# webradio.net
KiCad netlist of a schematic drawn in EAGLE
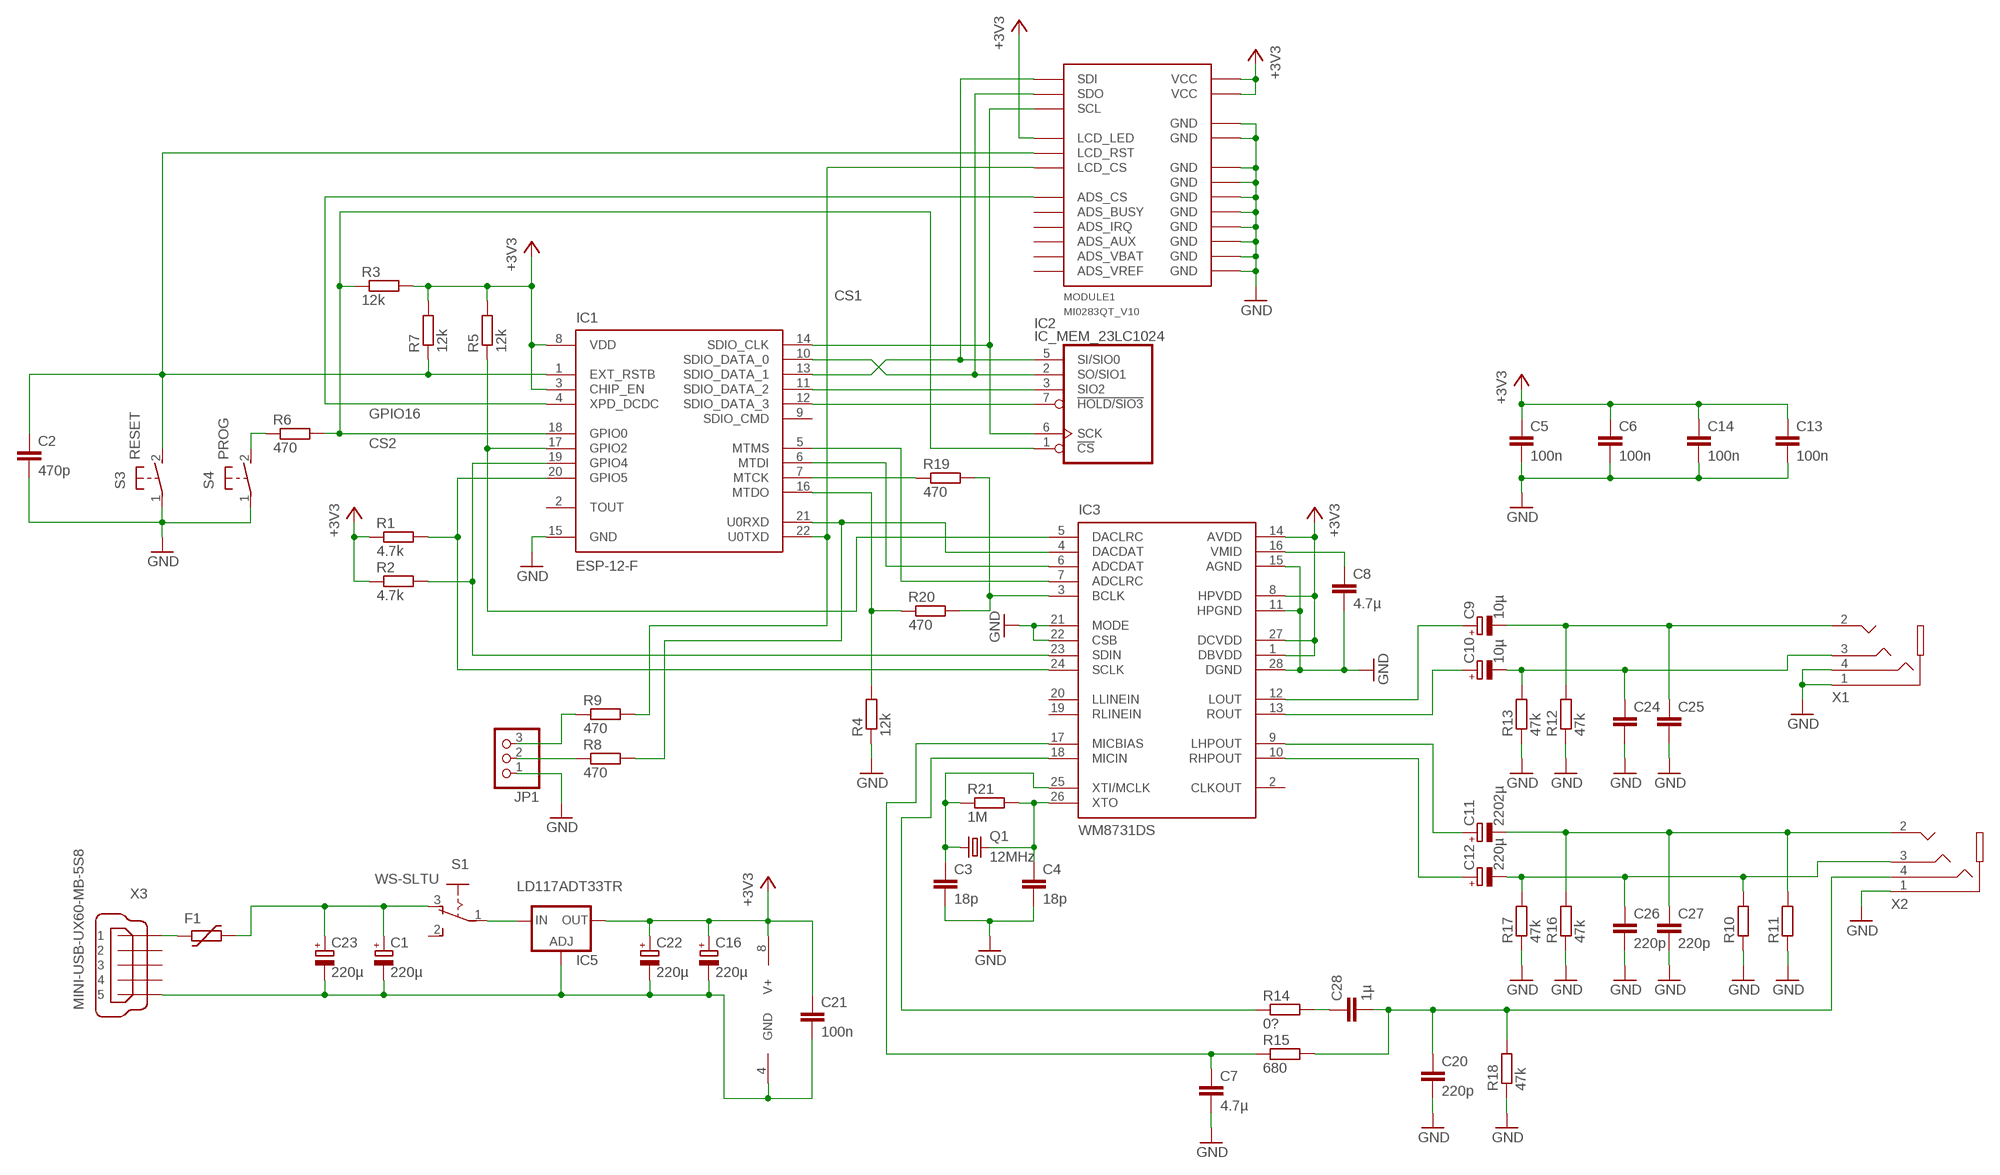
[diagram p0: schematic, sheet 1]

(export (version "E")
  (design (tool "Eeschema 10.0.6"))
  (components
    (comp (ref "C1")
      (value "220µ")
      (footprint "eagle-import:B_3528-21R")
      (libsource (lib "eagle-import") (part "CPOL-EUB/3528-21R"))
    )
    (comp (ref "C2")
      (value "470p")
      (footprint "eagle-import:C0805")
      (libsource (lib "eagle-import") (part "C-EUC0805"))
    )
    (comp (ref "C3")
      (value "18p")
      (footprint "eagle-import:C0805")
      (libsource (lib "eagle-import") (part "C-EUC0805"))
    )
    (comp (ref "C4")
      (value "18p")
      (footprint "eagle-import:C0805")
      (libsource (lib "eagle-import") (part "C-EUC0805"))
    )
    (comp (ref "C5")
      (value "100n")
      (footprint "eagle-import:C0805")
      (libsource (lib "eagle-import") (part "C-EUC0805"))
    )
    (comp (ref "C6")
      (value "100n")
      (footprint "eagle-import:C0805")
      (libsource (lib "eagle-import") (part "C-EUC0805"))
    )
    (comp (ref "C7")
      (value "4.7µ")
      (footprint "eagle-import:C0805")
      (libsource (lib "eagle-import") (part "C-EUC0805"))
    )
    (comp (ref "C8")
      (value "4.7µ")
      (footprint "eagle-import:C0805")
      (libsource (lib "eagle-import") (part "C-EUC0805"))
    )
    (comp (ref "C9")
      (value "10µ")
      (footprint "eagle-import:A_3216-18R")
      (libsource (lib "eagle-import") (part "CPOL-EUA/3216-18R"))
    )
    (comp (ref "C10")
      (value "10µ")
      (footprint "eagle-import:A_3216-18R")
      (libsource (lib "eagle-import") (part "CPOL-EUA/3216-18R"))
    )
    (comp (ref "C11")
      (value "2202µ")
      (footprint "eagle-import:D_7343-31R")
      (libsource (lib "eagle-import") (part "CPOL-EUD/7343-31R"))
    )
    (comp (ref "C12")
      (value "220µ")
      (footprint "eagle-import:D_7343-31R")
      (libsource (lib "eagle-import") (part "CPOL-EUD/7343-31R"))
    )
    (comp (ref "C13")
      (value "100n")
      (footprint "eagle-import:C0805")
      (libsource (lib "eagle-import") (part "C-EUC0805"))
    )
    (comp (ref "C14")
      (value "100n")
      (footprint "eagle-import:C0805")
      (libsource (lib "eagle-import") (part "C-EUC0805"))
    )
    (comp (ref "C16")
      (value "220µ")
      (footprint "eagle-import:B_3528-21R")
      (libsource (lib "eagle-import") (part "CPOL-EUB/3528-21R"))
    )
    (comp (ref "C20")
      (value "220p")
      (footprint "eagle-import:C0805")
      (libsource (lib "eagle-import") (part "C-EUC0805"))
    )
    (comp (ref "C21")
      (value "100n")
      (footprint "eagle-import:C0805")
      (libsource (lib "eagle-import") (part "C-EUC0805"))
    )
    (comp (ref "C22")
      (value "220µ")
      (footprint "eagle-import:B_3528-21R")
      (libsource (lib "eagle-import") (part "CPOL-EUB/3528-21R"))
    )
    (comp (ref "C23")
      (value "220µ")
      (footprint "eagle-import:B_3528-21R")
      (libsource (lib "eagle-import") (part "CPOL-EUB/3528-21R"))
    )
    (comp (ref "C24")
      (value "C-EUC0805")
      (footprint "eagle-import:C0805")
      (libsource (lib "eagle-import") (part "C-EUC0805"))
    )
    (comp (ref "C25")
      (value "C-EUC0805")
      (footprint "eagle-import:C0805")
      (libsource (lib "eagle-import") (part "C-EUC0805"))
    )
    (comp (ref "C26")
      (value "220p")
      (footprint "eagle-import:C0805")
      (libsource (lib "eagle-import") (part "C-EUC0805"))
    )
    (comp (ref "C27")
      (value "220p")
      (footprint "eagle-import:C0805")
      (libsource (lib "eagle-import") (part "C-EUC0805"))
    )
    (comp (ref "C28")
      (value "1µ")
      (footprint "eagle-import:C0805")
      (libsource (lib "eagle-import") (part "C-EUC0805"))
    )
    (comp (ref "F1")
      (value "FUSE_PTC-1812")
      (footprint "eagle-import:PTC1812L")
      (libsource (lib "eagle-import") (part "FUSE_PTC-1812"))
    )
    (comp (ref "IC1")
      (value "ESP-12-F")
      (footprint "eagle-import:ESP-12-F")
      (libsource (lib "eagle-import") (part "ESP-12-F"))
    )
    (comp (ref "IC2")
      (value "IC_MEM_23LC1024")
      (footprint "eagle-import:SOIC-8")
      (libsource (lib "eagle-import") (part "IC_MEM_23LC1024"))
    )
    (comp (ref "IC3")
      (value "WM8731DS")
      (footprint "eagle-import:SSOP28")
      (libsource (lib "eagle-import") (part "WM8731DS"))
    )
    (comp (ref "IC5")
      (value "LD117ADT33TR")
      (footprint "eagle-import:DPACK")
      (libsource (lib "eagle-import") (part "LD117A?DT33TR"))
    )
    (comp (ref "JP1")
      (value "PINHD-1X3/90")
      (footprint "eagle-import:1X03_90")
      (libsource (lib "eagle-import") (part "PINHD-1X3/90"))
    )
    (comp (ref "MODULE1")
      (value "MI0283QT_V10")
      (footprint "eagle-import:MI0283QT_V10")
      (libsource (lib "eagle-import") (part "MI0283QT_V10"))
    )
    (comp (ref "Q1")
      (value "12MHz")
      (footprint "eagle-import:HC49UP")
      (libsource (lib "eagle-import") (part "CRYSTALHC49UP"))
    )
    (comp (ref "R1")
      (value "4.7k")
      (footprint "eagle-import:R0805")
      (libsource (lib "eagle-import") (part "R-EU_R0805"))
    )
    (comp (ref "R2")
      (value "4.7k")
      (footprint "eagle-import:R0805")
      (libsource (lib "eagle-import") (part "R-EU_R0805"))
    )
    (comp (ref "R3")
      (value "12k")
      (footprint "eagle-import:R0805")
      (libsource (lib "eagle-import") (part "R-EU_R0805"))
    )
    (comp (ref "R4")
      (value "12k")
      (footprint "eagle-import:R0805")
      (libsource (lib "eagle-import") (part "R-EU_R0805"))
    )
    (comp (ref "R5")
      (value "12k")
      (footprint "eagle-import:R0805")
      (libsource (lib "eagle-import") (part "R-EU_R0805"))
    )
    (comp (ref "R6")
      (value "470")
      (footprint "eagle-import:R0805")
      (libsource (lib "eagle-import") (part "R-EU_R0805"))
    )
    (comp (ref "R7")
      (value "12k")
      (footprint "eagle-import:R0805")
      (libsource (lib "eagle-import") (part "R-EU_R0805"))
    )
    (comp (ref "R8")
      (value "470")
      (footprint "eagle-import:R0805")
      (libsource (lib "eagle-import") (part "R-EU_R0805"))
    )
    (comp (ref "R9")
      (value "470")
      (footprint "eagle-import:R0805")
      (libsource (lib "eagle-import") (part "R-EU_R0805"))
    )
    (comp (ref "R10")
      (value "R-EU_R0805")
      (footprint "eagle-import:R0805")
      (libsource (lib "eagle-import") (part "R-EU_R0805"))
    )
    (comp (ref "R11")
      (value "R-EU_R0805")
      (footprint "eagle-import:R0805")
      (libsource (lib "eagle-import") (part "R-EU_R0805"))
    )
    (comp (ref "R12")
      (value "47k")
      (footprint "eagle-import:R0805")
      (libsource (lib "eagle-import") (part "R-EU_R0805"))
    )
    (comp (ref "R13")
      (value "47k")
      (footprint "eagle-import:R0805")
      (libsource (lib "eagle-import") (part "R-EU_R0805"))
    )
    (comp (ref "R14")
      (value "0?")
      (footprint "eagle-import:R0805")
      (libsource (lib "eagle-import") (part "R-EU_R0805"))
    )
    (comp (ref "R15")
      (value "680")
      (footprint "eagle-import:R0805")
      (libsource (lib "eagle-import") (part "R-EU_R0805"))
    )
    (comp (ref "R16")
      (value "47k")
      (footprint "eagle-import:R0805")
      (libsource (lib "eagle-import") (part "R-EU_R0805"))
    )
    (comp (ref "R17")
      (value "47k")
      (footprint "eagle-import:R0805")
      (libsource (lib "eagle-import") (part "R-EU_R0805"))
    )
    (comp (ref "R18")
      (value "47k")
      (footprint "eagle-import:R0805")
      (libsource (lib "eagle-import") (part "R-EU_R0805"))
    )
    (comp (ref "R19")
      (value "470")
      (footprint "eagle-import:R0805")
      (libsource (lib "eagle-import") (part "R-EU_R0805"))
    )
    (comp (ref "R20")
      (value "470")
      (footprint "eagle-import:R0805")
      (libsource (lib "eagle-import") (part "R-EU_R0805"))
    )
    (comp (ref "R21")
      (value "1M")
      (footprint "eagle-import:R0805")
      (libsource (lib "eagle-import") (part "R-EU_R0805"))
    )
    (comp (ref "S1")
      (value "WS-SLTU")
      (footprint "eagle-import:450302014072")
      (libsource (lib "eagle-import") (part "WS-SLTU"))
    )
    (comp (ref "S3")
      (value "RESET")
      (footprint "eagle-import:B3F-31XX")
      (libsource (lib "eagle-import") (part "31-XX"))
    )
    (comp (ref "S4")
      (value "PROG")
      (footprint "eagle-import:B3F-31XX")
      (libsource (lib "eagle-import") (part "31-XX"))
    )
    (comp (ref "X1")
      (value "SJ-43514-SMT")
      (footprint "eagle-import:SJ-43514-SMT")
      (libsource (lib "eagle-import") (part "SJ-43514-SMT"))
    )
    (comp (ref "X2")
      (value "SJ-43514-SMT")
      (footprint "eagle-import:SJ-43514-SMT")
      (libsource (lib "eagle-import") (part "SJ-43514-SMT"))
    )
    (comp (ref "X3")
      (value "MINI-USB-UX60-MB-5S8")
      (footprint "eagle-import:UX60-MB-5S8")
      (libsource (lib "eagle-import") (part "MINI-USB-UX60-MB-5S8"))
    )
  )
  (nets
    (net (code "1") (name "+3V3") (class "Default")
      (node (ref "C13") (pin "1") (pinfunction "1_1") (pintype "passive"))
      (node (ref "C14") (pin "1") (pinfunction "1_1") (pintype "passive"))
      (node (ref "C16") (pin "+") (pinfunction "+_+") (pintype "passive"))
      (node (ref "C21") (pin "1") (pinfunction "1_1") (pintype "passive"))
      (node (ref "C22") (pin "+") (pinfunction "+_+") (pintype "passive"))
      (node (ref "C5") (pin "1") (pinfunction "1_1") (pintype "passive"))
      (node (ref "C6") (pin "1") (pinfunction "1_1") (pintype "passive"))
      (node (ref "IC1") (pin "3") (pinfunction "CHIP_EN_3") (pintype "input"))
      (node (ref "IC1") (pin "8") (pinfunction "VDD_8") (pintype "power_in"))
      (node (ref "IC2") (pin "8") (pinfunction "V+_8") (pintype "power_in"))
      (node (ref "IC3") (pin "1") (pinfunction "DBVDD_1") (pintype "power_in"))
      (node (ref "IC3") (pin "14") (pinfunction "AVDD_14") (pintype "power_in"))
      (node (ref "IC3") (pin "27") (pinfunction "DCVDD_27") (pintype "power_in"))
      (node (ref "IC3") (pin "8") (pinfunction "HPVDD_8") (pintype "power_in"))
      (node (ref "IC5") (pin "4") (pinfunction "OUT_4") (pintype "passive"))
      (node (ref "MODULE1") (pin "3_VCC") (pinfunction "VCC_3_VCC") (pintype "power_in"))
      (node (ref "MODULE1") (pin "4_VCC") (pinfunction "VCC_4_VCC") (pintype "power_in"))
      (node (ref "MODULE1") (pin "5_LCD_LED") (pinfunction "LCD_LED_5_LCD_LED") (pintype "input"))
      (node (ref "R1") (pin "1") (pinfunction "1_1") (pintype "passive"))
      (node (ref "R2") (pin "1") (pinfunction "1_1") (pintype "passive"))
      (node (ref "R3") (pin "2") (pinfunction "2_2") (pintype "passive"))
      (node (ref "R5") (pin "2") (pinfunction "2_2") (pintype "passive"))
      (node (ref "R7") (pin "2") (pinfunction "2_2") (pintype "passive"))
    )
    (net (code "2") (name "GND") (class "Default")
      (node (ref "C1") (pin "-") (pinfunction "-_-") (pintype "passive"))
      (node (ref "C13") (pin "2") (pinfunction "2_2") (pintype "passive"))
      (node (ref "C14") (pin "2") (pinfunction "2_2") (pintype "passive"))
      (node (ref "C16") (pin "-") (pinfunction "-_-") (pintype "passive"))
      (node (ref "C2") (pin "2") (pinfunction "2_2") (pintype "passive"))
      (node (ref "C20") (pin "2") (pinfunction "2_2") (pintype "passive"))
      (node (ref "C21") (pin "2") (pinfunction "2_2") (pintype "passive"))
      (node (ref "C22") (pin "-") (pinfunction "-_-") (pintype "passive"))
      (node (ref "C23") (pin "-") (pinfunction "-_-") (pintype "passive"))
      (node (ref "C24") (pin "2") (pinfunction "2_2") (pintype "passive"))
      (node (ref "C25") (pin "2") (pinfunction "2_2") (pintype "passive"))
      (node (ref "C26") (pin "2") (pinfunction "2_2") (pintype "passive"))
      (node (ref "C27") (pin "2") (pinfunction "2_2") (pintype "passive"))
      (node (ref "C3") (pin "2") (pinfunction "2_2") (pintype "passive"))
      (node (ref "C4") (pin "2") (pinfunction "2_2") (pintype "passive"))
      (node (ref "C5") (pin "2") (pinfunction "2_2") (pintype "passive"))
      (node (ref "C6") (pin "2") (pinfunction "2_2") (pintype "passive"))
      (node (ref "C7") (pin "2") (pinfunction "2_2") (pintype "passive"))
      (node (ref "C8") (pin "2") (pinfunction "2_2") (pintype "passive"))
      (node (ref "IC1") (pin "15") (pinfunction "GND_15") (pintype "power_in"))
      (node (ref "IC2") (pin "4") (pinfunction "GND_4") (pintype "power_in"))
      (node (ref "IC3") (pin "11") (pinfunction "HPGND_11") (pintype "power_in"))
      (node (ref "IC3") (pin "15") (pinfunction "AGND_15") (pintype "power_in"))
      (node (ref "IC3") (pin "21") (pinfunction "MODE_21") (pintype "input"))
      (node (ref "IC3") (pin "22") (pinfunction "CSB_22") (pintype "input"))
      (node (ref "IC3") (pin "28") (pinfunction "DGND_28") (pintype "power_in"))
      (node (ref "IC5") (pin "1") (pinfunction "ADJ_1") (pintype "input"))
      (node (ref "JP1") (pin "1") (pinfunction "1_1") (pintype "passive"))
      (node (ref "MODULE1") (pin "1_GND") (pinfunction "GND_1_GND") (pintype "power_in"))
      (node (ref "MODULE1") (pin "2_GND") (pinfunction "GND_2_GND") (pintype "power_in"))
      (node (ref "MODULE1") (pin "GND_1") (pinfunction "GND_GND_1") (pintype "power_in"))
      (node (ref "MODULE1") (pin "GND_2") (pinfunction "GND_GND_2") (pintype "power_in"))
      (node (ref "MODULE1") (pin "GND_3") (pinfunction "GND_GND_3") (pintype "power_in"))
      (node (ref "MODULE1") (pin "GND_4") (pinfunction "GND_GND_4") (pintype "power_in"))
      (node (ref "MODULE1") (pin "GND_5") (pinfunction "GND_GND_5") (pintype "power_in"))
      (node (ref "MODULE1") (pin "GND_6") (pinfunction "GND_GND_6") (pintype "power_in"))
      (node (ref "MODULE1") (pin "GND_7") (pinfunction "GND_GND_7") (pintype "power_in"))
      (node (ref "MODULE1") (pin "GND_8") (pinfunction "GND_GND_8") (pintype "power_in"))
      (node (ref "R10") (pin "1") (pinfunction "1_1") (pintype "passive"))
      (node (ref "R11") (pin "1") (pinfunction "1_1") (pintype "passive"))
      (node (ref "R12") (pin "1") (pinfunction "1_1") (pintype "passive"))
      (node (ref "R13") (pin "1") (pinfunction "1_1") (pintype "passive"))
      (node (ref "R16") (pin "1") (pinfunction "1_1") (pintype "passive"))
      (node (ref "R17") (pin "1") (pinfunction "1_1") (pintype "passive"))
      (node (ref "R18") (pin "1") (pinfunction "1_1") (pintype "passive"))
      (node (ref "R4") (pin "1") (pinfunction "1_1") (pintype "passive"))
      (node (ref "S3") (pin "1") (pinfunction "P_1") (pintype "passive"))
      (node (ref "S4") (pin "1") (pinfunction "P_1") (pintype "passive"))
      (node (ref "X1") (pin "1") (pinfunction "1_1") (pintype "passive"))
      (node (ref "X1") (pin "4") (pinfunction "4_4") (pintype "passive"))
      (node (ref "X2") (pin "1") (pinfunction "1_1") (pintype "passive"))
      (node (ref "X3") (pin "5") (pinfunction "5_5") (pintype "input"))
    )
    (net (code "3") (name "Net-(C10-Pad-)") (class "Default")
      (node (ref "C10") (pin "-") (pinfunction "-_-") (pintype "passive"))
      (node (ref "C24") (pin "1") (pinfunction "1_1") (pintype "passive"))
      (node (ref "R13") (pin "2") (pinfunction "2_2") (pintype "passive"))
      (node (ref "X1") (pin "3") (pinfunction "3_3") (pintype "passive"))
    )
    (net (code "4") (name "Net-(C11-Pad-)") (class "Default")
      (node (ref "C11") (pin "-") (pinfunction "-_-") (pintype "passive"))
      (node (ref "C27") (pin "1") (pinfunction "1_1") (pintype "passive"))
      (node (ref "R11") (pin "2") (pinfunction "2_2") (pintype "passive"))
      (node (ref "R16") (pin "2") (pinfunction "2_2") (pintype "passive"))
      (node (ref "X2") (pin "2") (pinfunction "2_2") (pintype "passive"))
    )
    (net (code "5") (name "Net-(C12-Pad-)") (class "Default")
      (node (ref "C12") (pin "-") (pinfunction "-_-") (pintype "passive"))
      (node (ref "C26") (pin "1") (pinfunction "1_1") (pintype "passive"))
      (node (ref "R10") (pin "2") (pinfunction "2_2") (pintype "passive"))
      (node (ref "R17") (pin "2") (pinfunction "2_2") (pintype "passive"))
      (node (ref "X2") (pin "3") (pinfunction "3_3") (pintype "passive"))
    )
    (net (code "6") (name "Net-(C20-Pad1)") (class "Default")
      (node (ref "C20") (pin "1") (pinfunction "1_1") (pintype "passive"))
      (node (ref "C28") (pin "2") (pinfunction "2_2") (pintype "passive"))
      (node (ref "R15") (pin "2") (pinfunction "2_2") (pintype "passive"))
      (node (ref "R18") (pin "2") (pinfunction "2_2") (pintype "passive"))
      (node (ref "X2") (pin "4") (pinfunction "4_4") (pintype "passive"))
    )
    (net (code "7") (name "Net-(C25-Pad1)") (class "Default")
      (node (ref "C25") (pin "1") (pinfunction "1_1") (pintype "passive"))
      (node (ref "C9") (pin "-") (pinfunction "-_-") (pintype "passive"))
      (node (ref "R12") (pin "2") (pinfunction "2_2") (pintype "passive"))
      (node (ref "X1") (pin "2") (pinfunction "2_2") (pintype "passive"))
    )
    (net (code "8") (name "Net-(C28-Pad1)") (class "Default")
      (node (ref "C28") (pin "1") (pinfunction "1_1") (pintype "passive"))
      (node (ref "R14") (pin "2") (pinfunction "2_2") (pintype "passive"))
    )
    (net (code "9") (name "Net-(F1-Pad1)") (class "Default")
      (node (ref "F1") (pin "1") (pinfunction "1_1") (pintype "passive"))
      (node (ref "X3") (pin "1") (pinfunction "1_1") (pintype "input"))
    )
    (net (code "10") (name "Net-(IC1-EXT_RSTB)") (class "Default")
      (node (ref "C2") (pin "1") (pinfunction "1_1") (pintype "passive"))
      (node (ref "IC1") (pin "1") (pinfunction "EXT_RSTB_1") (pintype "input"))
      (node (ref "MODULE1") (pin "6_LCD_RST") (pinfunction "LCD_RST_6_LCD_RST") (pintype "input"))
      (node (ref "R7") (pin "1") (pinfunction "1_1") (pintype "passive"))
      (node (ref "S3") (pin "2") (pinfunction "S_2") (pintype "passive"))
    )
    (net (code "11") (name "Net-(IC1-GPIO0)") (class "Default")
      (node (ref "IC1") (pin "18") (pinfunction "GPIO0_18") (pintype "bidirectional"))
      (node (ref "IC2") (pin "1") (pinfunction "~{CS}_1") (pintype "input"))
      (node (ref "R3") (pin "1") (pinfunction "1_1") (pintype "passive"))
      (node (ref "R6") (pin "2") (pinfunction "2_2") (pintype "passive"))
    )
    (net (code "12") (name "Net-(IC1-GPIO2)") (class "Default")
      (node (ref "IC1") (pin "17") (pinfunction "GPIO2_17") (pintype "bidirectional"))
      (node (ref "IC3") (pin "5") (pinfunction "DACLRC_5") (pintype "bidirectional"))
      (node (ref "R5") (pin "1") (pinfunction "1_1") (pintype "passive"))
    )
    (net (code "13") (name "Net-(IC1-GPIO4)") (class "Default")
      (node (ref "IC1") (pin "19") (pinfunction "GPIO4_19") (pintype "bidirectional"))
      (node (ref "IC3") (pin "23") (pinfunction "SDIN_23") (pintype "bidirectional"))
      (node (ref "R2") (pin "2") (pinfunction "2_2") (pintype "passive"))
    )
    (net (code "14") (name "Net-(IC1-GPIO5)") (class "Default")
      (node (ref "IC1") (pin "20") (pinfunction "GPIO5_20") (pintype "bidirectional"))
      (node (ref "IC3") (pin "24") (pinfunction "SCLK_24") (pintype "input"))
      (node (ref "R1") (pin "2") (pinfunction "2_2") (pintype "passive"))
    )
    (net (code "15") (name "Net-(IC1-MTCK)") (class "Default")
      (node (ref "IC1") (pin "7") (pinfunction "MTCK_7") (pintype "bidirectional"))
      (node (ref "R19") (pin "1") (pinfunction "1_1") (pintype "passive"))
    )
    (net (code "16") (name "Net-(IC1-MTDI)") (class "Default")
      (node (ref "IC1") (pin "6") (pinfunction "MTDI_6") (pintype "bidirectional"))
      (node (ref "IC3") (pin "6") (pinfunction "ADCDAT_6") (pintype "output"))
    )
    (net (code "17") (name "Net-(IC1-MTDO)") (class "Default")
      (node (ref "IC1") (pin "16") (pinfunction "MTDO_16") (pintype "bidirectional"))
      (node (ref "R20") (pin "1") (pinfunction "1_1") (pintype "passive"))
      (node (ref "R4") (pin "2") (pinfunction "2_2") (pintype "passive"))
    )
    (net (code "18") (name "Net-(IC1-MTMS)") (class "Default")
      (node (ref "IC1") (pin "5") (pinfunction "MTMS_5") (pintype "bidirectional"))
      (node (ref "IC3") (pin "7") (pinfunction "ADCLRC_7") (pintype "bidirectional"))
    )
    (net (code "19") (name "Net-(IC1-SDIO_CLK)") (class "Default")
      (node (ref "IC1") (pin "14") (pinfunction "SDIO_CLK_14") (pintype "bidirectional"))
      (node (ref "IC2") (pin "6") (pinfunction "SCK_6") (pintype "input"))
      (node (ref "MODULE1") (pin "10_SCL") (pinfunction "SCL_10_SCL") (pintype "input"))
    )
    (net (code "20") (name "Net-(IC1-SDIO_DATA_0)") (class "Default")
      (node (ref "IC1") (pin "10") (pinfunction "SDIO_DATA_0_10") (pintype "bidirectional"))
      (node (ref "IC2") (pin "2") (pinfunction "SO/SIO1_2") (pintype "bidirectional"))
      (node (ref "MODULE1") (pin "9_SDO") (pinfunction "SDO_9_SDO") (pintype "output"))
    )
    (net (code "21") (name "Net-(IC1-SDIO_DATA_1)") (class "Default")
      (node (ref "IC1") (pin "13") (pinfunction "SDIO_DATA_1_13") (pintype "bidirectional"))
      (node (ref "IC2") (pin "5") (pinfunction "SI/SIO0_5") (pintype "bidirectional"))
      (node (ref "MODULE1") (pin "8_SDI") (pinfunction "SDI_8_SDI") (pintype "input"))
    )
    (net (code "22") (name "Net-(IC1-SDIO_DATA_2)") (class "Default")
      (node (ref "IC1") (pin "11") (pinfunction "SDIO_DATA_2_11") (pintype "bidirectional"))
      (node (ref "IC2") (pin "3") (pinfunction "SIO2_3") (pintype "bidirectional"))
    )
    (net (code "23") (name "Net-(IC1-SDIO_DATA_3)") (class "Default")
      (node (ref "IC1") (pin "12") (pinfunction "SDIO_DATA_3_12") (pintype "bidirectional"))
      (node (ref "IC2") (pin "7") (pinfunction "~{HOLD/SIO3}_7") (pintype "input"))
    )
    (net (code "24") (name "Net-(IC1-U0RXD)") (class "Default")
      (node (ref "IC1") (pin "21") (pinfunction "U0RXD_21") (pintype "bidirectional"))
      (node (ref "IC3") (pin "4") (pinfunction "DACDAT_4") (pintype "input"))
      (node (ref "R8") (pin "2") (pinfunction "2_2") (pintype "passive"))
    )
    (net (code "25") (name "Net-(IC1-U0TXD)") (class "Default")
      (node (ref "IC1") (pin "22") (pinfunction "U0TXD_22") (pintype "bidirectional"))
      (node (ref "MODULE1") (pin "7_LCD_CS") (pinfunction "LCD_CS_7_LCD_CS") (pintype "input"))
      (node (ref "R9") (pin "2") (pinfunction "2_2") (pintype "passive"))
    )
    (net (code "26") (name "Net-(IC1-XPD_DCDC)") (class "Default")
      (node (ref "IC1") (pin "4") (pinfunction "XPD_DCDC_4") (pintype "bidirectional"))
      (node (ref "MODULE1") (pin "11_ADS_CS") (pinfunction "ADS_CS_11_ADS_CS") (pintype "input"))
    )
    (net (code "27") (name "Net-(IC3-BCLK)") (class "Default")
      (node (ref "IC3") (pin "3") (pinfunction "BCLK_3") (pintype "bidirectional"))
      (node (ref "R19") (pin "2") (pinfunction "2_2") (pintype "passive"))
      (node (ref "R20") (pin "2") (pinfunction "2_2") (pintype "passive"))
    )
    (net (code "28") (name "Net-(IC3-LHPOUT)") (class "Default")
      (node (ref "C11") (pin "+") (pinfunction "+_+") (pintype "passive"))
      (node (ref "IC3") (pin "9") (pinfunction "LHPOUT_9") (pintype "output"))
    )
    (net (code "29") (name "Net-(IC3-LOUT)") (class "Default")
      (node (ref "C9") (pin "+") (pinfunction "+_+") (pintype "passive"))
      (node (ref "IC3") (pin "12") (pinfunction "LOUT_12") (pintype "output"))
    )
    (net (code "30") (name "Net-(IC3-MICBIAS)") (class "Default")
      (node (ref "C7") (pin "1") (pinfunction "1_1") (pintype "passive"))
      (node (ref "IC3") (pin "17") (pinfunction "MICBIAS_17") (pintype "output"))
      (node (ref "R15") (pin "1") (pinfunction "1_1") (pintype "passive"))
    )
    (net (code "31") (name "Net-(IC3-MICIN)") (class "Default")
      (node (ref "IC3") (pin "18") (pinfunction "MICIN_18") (pintype "input"))
      (node (ref "R14") (pin "1") (pinfunction "1_1") (pintype "passive"))
    )
    (net (code "32") (name "Net-(IC3-RHPOUT)") (class "Default")
      (node (ref "C12") (pin "+") (pinfunction "+_+") (pintype "passive"))
      (node (ref "IC3") (pin "10") (pinfunction "RHPOUT_10") (pintype "output"))
    )
    (net (code "33") (name "Net-(IC3-ROUT)") (class "Default")
      (node (ref "C10") (pin "+") (pinfunction "+_+") (pintype "passive"))
      (node (ref "IC3") (pin "13") (pinfunction "ROUT_13") (pintype "output"))
    )
    (net (code "34") (name "Net-(IC3-VMID)") (class "Default")
      (node (ref "C8") (pin "1") (pinfunction "1_1") (pintype "passive"))
      (node (ref "IC3") (pin "16") (pinfunction "VMID_16") (pintype "output"))
    )
    (net (code "35") (name "Net-(IC3-XTI{slash}MCLK)") (class "Default")
      (node (ref "C3") (pin "1") (pinfunction "1_1") (pintype "passive"))
      (node (ref "IC3") (pin "25") (pinfunction "XTI/MCLK_25") (pintype "input"))
      (node (ref "Q1") (pin "1") (pinfunction "1_1") (pintype "passive"))
      (node (ref "R21") (pin "1") (pinfunction "1_1") (pintype "passive"))
    )
    (net (code "36") (name "Net-(IC3-XTO)") (class "Default")
      (node (ref "C4") (pin "1") (pinfunction "1_1") (pintype "passive"))
      (node (ref "IC3") (pin "26") (pinfunction "XTO_26") (pintype "output"))
      (node (ref "Q1") (pin "2") (pinfunction "2_2") (pintype "passive"))
      (node (ref "R21") (pin "2") (pinfunction "2_2") (pintype "passive"))
    )
    (net (code "37") (name "Net-(IC5-IN)") (class "Default")
      (node (ref "IC5") (pin "3") (pinfunction "IN_3") (pintype "input"))
      (node (ref "S1") (pin "1") (pinfunction "P_1") (pintype "passive"))
    )
    (net (code "38") (name "Net-(JP1-Pad2)") (class "Default")
      (node (ref "JP1") (pin "2") (pinfunction "2_2") (pintype "passive"))
      (node (ref "R8") (pin "1") (pinfunction "1_1") (pintype "passive"))
    )
    (net (code "39") (name "Net-(JP1-Pad3)") (class "Default")
      (node (ref "JP1") (pin "3") (pinfunction "3_3") (pintype "passive"))
      (node (ref "R9") (pin "1") (pinfunction "1_1") (pintype "passive"))
    )
    (net (code "40") (name "Net-(S1-O)") (class "Default")
      (node (ref "C1") (pin "+") (pinfunction "+_+") (pintype "passive"))
      (node (ref "C23") (pin "+") (pinfunction "+_+") (pintype "passive"))
      (node (ref "F1") (pin "2") (pinfunction "2_2") (pintype "passive"))
      (node (ref "S1") (pin "3") (pinfunction "O_3") (pintype "passive"))
    )
    (net (code "41") (name "Net-(S4-S)") (class "Default")
      (node (ref "R6") (pin "1") (pinfunction "1_1") (pintype "passive"))
      (node (ref "S4") (pin "2") (pinfunction "S_2") (pintype "passive"))
    )
    (net (code "42") (name "unconnected-(IC1-SDIO_CMD-Pad9)") (class "Default")
      (node (ref "IC1") (pin "9") (pinfunction "SDIO_CMD_9") (pintype "bidirectional"))
    )
    (net (code "43") (name "unconnected-(IC1-TOUT-Pad2)") (class "Default")
      (node (ref "IC1") (pin "2") (pinfunction "TOUT_2") (pintype "input"))
    )
    (net (code "44") (name "unconnected-(IC3-CLKOUT-Pad2)") (class "Default")
      (node (ref "IC3") (pin "2") (pinfunction "CLKOUT_2") (pintype "output"))
    )
    (net (code "45") (name "unconnected-(IC3-LLINEIN-Pad20)") (class "Default")
      (node (ref "IC3") (pin "20") (pinfunction "LLINEIN_20") (pintype "input"))
    )
    (net (code "46") (name "unconnected-(IC3-RLINEIN-Pad19)") (class "Default")
      (node (ref "IC3") (pin "19") (pinfunction "RLINEIN_19") (pintype "input"))
    )
    (net (code "47") (name "unconnected-(MODULE1-ADS_AUX-Pad14_ADS_AUX)") (class "Default")
      (node (ref "MODULE1") (pin "14_ADS_AUX") (pinfunction "ADS_AUX_14_ADS_AUX") (pintype "input"))
    )
    (net (code "48") (name "unconnected-(MODULE1-ADS_BUSY-Pad12_ADS_BUSY)") (class "Default")
      (node (ref "MODULE1") (pin "12_ADS_BUSY") (pinfunction "ADS_BUSY_12_ADS_BUSY") (pintype "output"))
    )
    (net (code "49") (name "unconnected-(MODULE1-ADS_IRQ-Pad13_ADS_IRQ)") (class "Default")
      (node (ref "MODULE1") (pin "13_ADS_IRQ") (pinfunction "ADS_IRQ_13_ADS_IRQ") (pintype "output"))
    )
    (net (code "50") (name "unconnected-(MODULE1-ADS_VBAT-Pad15_ADS_VBAT)") (class "Default")
      (node (ref "MODULE1") (pin "15_ADS_VBAT") (pinfunction "ADS_VBAT_15_ADS_VBAT") (pintype "input"))
    )
    (net (code "51") (name "unconnected-(MODULE1-ADS_VREF-Pad16_ADS_VREF)") (class "Default")
      (node (ref "MODULE1") (pin "16_ADS_VREF") (pinfunction "ADS_VREF_16_ADS_VREF") (pintype "input"))
    )
    (net (code "52") (name "unconnected-(S1-S-Pad2)") (class "Default")
      (node (ref "S1") (pin "2") (pinfunction "S_2") (pintype "passive"))
    )
    (net (code "53") (name "unconnected-(X3-Pad2)") (class "Default")
      (node (ref "X3") (pin "2") (pinfunction "2_2") (pintype "input"))
    )
    (net (code "54") (name "unconnected-(X3-Pad3)") (class "Default")
      (node (ref "X3") (pin "3") (pinfunction "3_3") (pintype "input"))
    )
    (net (code "55") (name "unconnected-(X3-Pad4)") (class "Default")
      (node (ref "X3") (pin "4") (pinfunction "4_4") (pintype "input"))
    )
  )
)
